# BMS_Enerdel_Adapter_Fuse_Holder_rev1.net
KiCad netlist of a schematic drawn in EAGLE
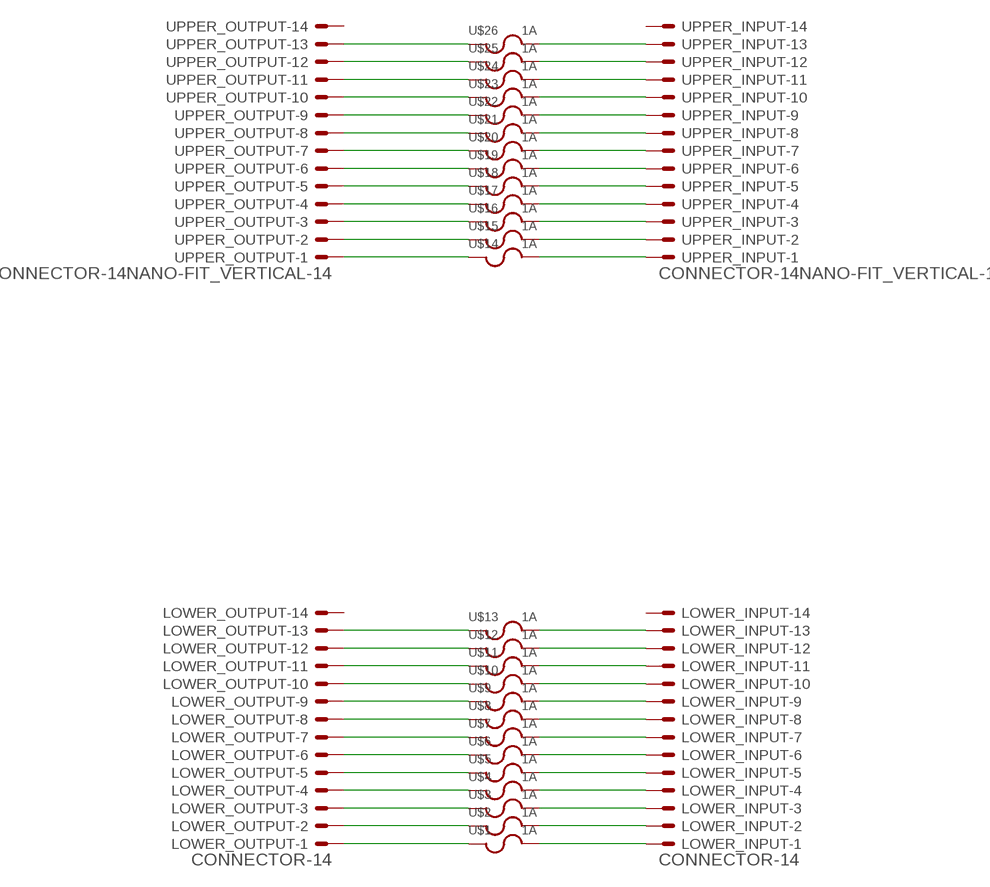
[diagram p0: schematic, sheet 1]

(export (version "E")
  (design (tool "Eeschema 10.0.6"))
  (components
    (comp (ref "LOWER_INPUT")
      (value "CONNECTOR-14")
      (footprint "eagle-import:MINIFIT_5566-14")
      (libsource (lib "eagle-import") (part "CONNECTOR-14"))
    )
    (comp (ref "LOWER_OUTPUT")
      (value "CONNECTOR-14")
      (footprint "eagle-import:MINIFIT_5566-14")
      (libsource (lib "eagle-import") (part "CONNECTOR-14"))
    )
    (comp (ref "U$1")
      (value "1A")
      (footprint "eagle-import:0751.0110")
      (libsource (lib "eagle-import") (part "FUSE_5X20MM"))
    )
    (comp (ref "U$2")
      (value "1A")
      (footprint "eagle-import:0751.0110")
      (libsource (lib "eagle-import") (part "FUSE_5X20MM"))
    )
    (comp (ref "U$3")
      (value "1A")
      (footprint "eagle-import:0751.0110")
      (libsource (lib "eagle-import") (part "FUSE_5X20MM"))
    )
    (comp (ref "U$4")
      (value "1A")
      (footprint "eagle-import:0751.0110")
      (libsource (lib "eagle-import") (part "FUSE_5X20MM"))
    )
    (comp (ref "U$5")
      (value "1A")
      (footprint "eagle-import:0751.0110")
      (libsource (lib "eagle-import") (part "FUSE_5X20MM"))
    )
    (comp (ref "U$6")
      (value "1A")
      (footprint "eagle-import:0751.0110")
      (libsource (lib "eagle-import") (part "FUSE_5X20MM"))
    )
    (comp (ref "U$7")
      (value "1A")
      (footprint "eagle-import:0751.0110")
      (libsource (lib "eagle-import") (part "FUSE_5X20MM"))
    )
    (comp (ref "U$8")
      (value "1A")
      (footprint "eagle-import:0751.0110")
      (libsource (lib "eagle-import") (part "FUSE_5X20MM"))
    )
    (comp (ref "U$9")
      (value "1A")
      (footprint "eagle-import:0751.0110")
      (libsource (lib "eagle-import") (part "FUSE_5X20MM"))
    )
    (comp (ref "U$10")
      (value "1A")
      (footprint "eagle-import:0751.0110")
      (libsource (lib "eagle-import") (part "FUSE_5X20MM"))
    )
    (comp (ref "U$11")
      (value "1A")
      (footprint "eagle-import:0751.0110")
      (libsource (lib "eagle-import") (part "FUSE_5X20MM"))
    )
    (comp (ref "U$12")
      (value "1A")
      (footprint "eagle-import:0751.0110")
      (libsource (lib "eagle-import") (part "FUSE_5X20MM"))
    )
    (comp (ref "U$13")
      (value "1A")
      (footprint "eagle-import:0751.0110")
      (libsource (lib "eagle-import") (part "FUSE_5X20MM"))
    )
    (comp (ref "U$14")
      (value "1A")
      (footprint "eagle-import:0751.0110")
      (libsource (lib "eagle-import") (part "FUSE_5X20MM"))
    )
    (comp (ref "U$15")
      (value "1A")
      (footprint "eagle-import:0751.0110")
      (libsource (lib "eagle-import") (part "FUSE_5X20MM"))
    )
    (comp (ref "U$16")
      (value "1A")
      (footprint "eagle-import:0751.0110")
      (libsource (lib "eagle-import") (part "FUSE_5X20MM"))
    )
    (comp (ref "U$17")
      (value "1A")
      (footprint "eagle-import:0751.0110")
      (libsource (lib "eagle-import") (part "FUSE_5X20MM"))
    )
    (comp (ref "U$18")
      (value "1A")
      (footprint "eagle-import:0751.0110")
      (libsource (lib "eagle-import") (part "FUSE_5X20MM"))
    )
    (comp (ref "U$19")
      (value "1A")
      (footprint "eagle-import:0751.0110")
      (libsource (lib "eagle-import") (part "FUSE_5X20MM"))
    )
    (comp (ref "U$20")
      (value "1A")
      (footprint "eagle-import:0751.0110")
      (libsource (lib "eagle-import") (part "FUSE_5X20MM"))
    )
    (comp (ref "U$21")
      (value "1A")
      (footprint "eagle-import:0751.0110")
      (libsource (lib "eagle-import") (part "FUSE_5X20MM"))
    )
    (comp (ref "U$22")
      (value "1A")
      (footprint "eagle-import:0751.0110")
      (libsource (lib "eagle-import") (part "FUSE_5X20MM"))
    )
    (comp (ref "U$23")
      (value "1A")
      (footprint "eagle-import:0751.0110")
      (libsource (lib "eagle-import") (part "FUSE_5X20MM"))
    )
    (comp (ref "U$24")
      (value "1A")
      (footprint "eagle-import:0751.0110")
      (libsource (lib "eagle-import") (part "FUSE_5X20MM"))
    )
    (comp (ref "U$25")
      (value "1A")
      (footprint "eagle-import:0751.0110")
      (libsource (lib "eagle-import") (part "FUSE_5X20MM"))
    )
    (comp (ref "U$26")
      (value "1A")
      (footprint "eagle-import:0751.0110")
      (libsource (lib "eagle-import") (part "FUSE_5X20MM"))
    )
    (comp (ref "UPPER_INPUT")
      (value "CONNECTOR-14NANO-FIT_VERTICAL-14")
      (footprint "eagle-import:NANO-FIT_VERTICAL-14")
      (libsource (lib "eagle-import") (part "CONNECTOR-14NANO-FIT_VERTICAL-14"))
    )
    (comp (ref "UPPER_OUTPUT")
      (value "CONNECTOR-14NANO-FIT_VERTICAL-14")
      (footprint "eagle-import:NANO-FIT_VERTICAL-14")
      (libsource (lib "eagle-import") (part "CONNECTOR-14NANO-FIT_VERTICAL-14"))
    )
  )
  (nets
    (net (code "1") (name "Net-(LOWER_INPUTA-S)") (class "Default")
      (node (ref "LOWER_INPUT") (pin "1") (pinfunction "S_1") (pintype "passive"))
      (node (ref "U$1") (pin "R1") (pinfunction "2_R1") (pintype "bidirectional"))
      (node (ref "U$1") (pin "R2") (pinfunction "2_R2") (pintype "bidirectional"))
    )
    (net (code "2") (name "Net-(LOWER_INPUTB-S)") (class "Default")
      (node (ref "LOWER_INPUT") (pin "10") (pinfunction "S_10") (pintype "passive"))
      (node (ref "U$10") (pin "R1") (pinfunction "2_R1") (pintype "bidirectional"))
      (node (ref "U$10") (pin "R2") (pinfunction "2_R2") (pintype "bidirectional"))
    )
    (net (code "3") (name "Net-(LOWER_INPUTC-S)") (class "Default")
      (node (ref "LOWER_INPUT") (pin "11") (pinfunction "S_11") (pintype "passive"))
      (node (ref "U$11") (pin "R1") (pinfunction "2_R1") (pintype "bidirectional"))
      (node (ref "U$11") (pin "R2") (pinfunction "2_R2") (pintype "bidirectional"))
    )
    (net (code "4") (name "Net-(LOWER_INPUTD-S)") (class "Default")
      (node (ref "LOWER_INPUT") (pin "12") (pinfunction "S_12") (pintype "passive"))
      (node (ref "U$12") (pin "R1") (pinfunction "2_R1") (pintype "bidirectional"))
      (node (ref "U$12") (pin "R2") (pinfunction "2_R2") (pintype "bidirectional"))
    )
    (net (code "5") (name "Net-(LOWER_INPUTE-S)") (class "Default")
      (node (ref "LOWER_INPUT") (pin "13") (pinfunction "S_13") (pintype "passive"))
      (node (ref "U$13") (pin "R1") (pinfunction "2_R1") (pintype "bidirectional"))
      (node (ref "U$13") (pin "R2") (pinfunction "2_R2") (pintype "bidirectional"))
    )
    (net (code "6") (name "Net-(LOWER_INPUTG-S)") (class "Default")
      (node (ref "LOWER_INPUT") (pin "2") (pinfunction "S_2") (pintype "passive"))
      (node (ref "U$2") (pin "R1") (pinfunction "2_R1") (pintype "bidirectional"))
      (node (ref "U$2") (pin "R2") (pinfunction "2_R2") (pintype "bidirectional"))
    )
    (net (code "7") (name "Net-(LOWER_INPUTH-S)") (class "Default")
      (node (ref "LOWER_INPUT") (pin "3") (pinfunction "S_3") (pintype "passive"))
      (node (ref "U$3") (pin "R1") (pinfunction "2_R1") (pintype "bidirectional"))
      (node (ref "U$3") (pin "R2") (pinfunction "2_R2") (pintype "bidirectional"))
    )
    (net (code "8") (name "Net-(LOWER_INPUTI-S)") (class "Default")
      (node (ref "LOWER_INPUT") (pin "4") (pinfunction "S_4") (pintype "passive"))
      (node (ref "U$4") (pin "R1") (pinfunction "2_R1") (pintype "bidirectional"))
      (node (ref "U$4") (pin "R2") (pinfunction "2_R2") (pintype "bidirectional"))
    )
    (net (code "9") (name "Net-(LOWER_INPUTJ-S)") (class "Default")
      (node (ref "LOWER_INPUT") (pin "5") (pinfunction "S_5") (pintype "passive"))
      (node (ref "U$5") (pin "R1") (pinfunction "2_R1") (pintype "bidirectional"))
      (node (ref "U$5") (pin "R2") (pinfunction "2_R2") (pintype "bidirectional"))
    )
    (net (code "10") (name "Net-(LOWER_INPUTK-S)") (class "Default")
      (node (ref "LOWER_INPUT") (pin "6") (pinfunction "S_6") (pintype "passive"))
      (node (ref "U$6") (pin "R1") (pinfunction "2_R1") (pintype "bidirectional"))
      (node (ref "U$6") (pin "R2") (pinfunction "2_R2") (pintype "bidirectional"))
    )
    (net (code "11") (name "Net-(LOWER_INPUTL-S)") (class "Default")
      (node (ref "LOWER_INPUT") (pin "7") (pinfunction "S_7") (pintype "passive"))
      (node (ref "U$7") (pin "R1") (pinfunction "2_R1") (pintype "bidirectional"))
      (node (ref "U$7") (pin "R2") (pinfunction "2_R2") (pintype "bidirectional"))
    )
    (net (code "12") (name "Net-(LOWER_INPUTM-S)") (class "Default")
      (node (ref "LOWER_INPUT") (pin "8") (pinfunction "S_8") (pintype "passive"))
      (node (ref "U$8") (pin "R1") (pinfunction "2_R1") (pintype "bidirectional"))
      (node (ref "U$8") (pin "R2") (pinfunction "2_R2") (pintype "bidirectional"))
    )
    (net (code "13") (name "Net-(LOWER_INPUTN-S)") (class "Default")
      (node (ref "LOWER_INPUT") (pin "9") (pinfunction "S_9") (pintype "passive"))
      (node (ref "U$9") (pin "R1") (pinfunction "2_R1") (pintype "bidirectional"))
      (node (ref "U$9") (pin "R2") (pinfunction "2_R2") (pintype "bidirectional"))
    )
    (net (code "14") (name "Net-(LOWER_OUTPUTA-S)") (class "Default")
      (node (ref "LOWER_OUTPUT") (pin "1") (pinfunction "S_1") (pintype "passive"))
      (node (ref "U$1") (pin "L1") (pinfunction "1_L1") (pintype "bidirectional"))
      (node (ref "U$1") (pin "L2") (pinfunction "1_L2") (pintype "bidirectional"))
    )
    (net (code "15") (name "Net-(LOWER_OUTPUTB-S)") (class "Default")
      (node (ref "LOWER_OUTPUT") (pin "10") (pinfunction "S_10") (pintype "passive"))
      (node (ref "U$10") (pin "L1") (pinfunction "1_L1") (pintype "bidirectional"))
      (node (ref "U$10") (pin "L2") (pinfunction "1_L2") (pintype "bidirectional"))
    )
    (net (code "16") (name "Net-(LOWER_OUTPUTC-S)") (class "Default")
      (node (ref "LOWER_OUTPUT") (pin "11") (pinfunction "S_11") (pintype "passive"))
      (node (ref "U$11") (pin "L1") (pinfunction "1_L1") (pintype "bidirectional"))
      (node (ref "U$11") (pin "L2") (pinfunction "1_L2") (pintype "bidirectional"))
    )
    (net (code "17") (name "Net-(LOWER_OUTPUTD-S)") (class "Default")
      (node (ref "LOWER_OUTPUT") (pin "12") (pinfunction "S_12") (pintype "passive"))
      (node (ref "U$12") (pin "L1") (pinfunction "1_L1") (pintype "bidirectional"))
      (node (ref "U$12") (pin "L2") (pinfunction "1_L2") (pintype "bidirectional"))
    )
    (net (code "18") (name "Net-(LOWER_OUTPUTE-S)") (class "Default")
      (node (ref "LOWER_OUTPUT") (pin "13") (pinfunction "S_13") (pintype "passive"))
      (node (ref "U$13") (pin "L1") (pinfunction "1_L1") (pintype "bidirectional"))
      (node (ref "U$13") (pin "L2") (pinfunction "1_L2") (pintype "bidirectional"))
    )
    (net (code "19") (name "Net-(LOWER_OUTPUTG-S)") (class "Default")
      (node (ref "LOWER_OUTPUT") (pin "2") (pinfunction "S_2") (pintype "passive"))
      (node (ref "U$2") (pin "L1") (pinfunction "1_L1") (pintype "bidirectional"))
      (node (ref "U$2") (pin "L2") (pinfunction "1_L2") (pintype "bidirectional"))
    )
    (net (code "20") (name "Net-(LOWER_OUTPUTH-S)") (class "Default")
      (node (ref "LOWER_OUTPUT") (pin "3") (pinfunction "S_3") (pintype "passive"))
      (node (ref "U$3") (pin "L1") (pinfunction "1_L1") (pintype "bidirectional"))
      (node (ref "U$3") (pin "L2") (pinfunction "1_L2") (pintype "bidirectional"))
    )
    (net (code "21") (name "Net-(LOWER_OUTPUTI-S)") (class "Default")
      (node (ref "LOWER_OUTPUT") (pin "4") (pinfunction "S_4") (pintype "passive"))
      (node (ref "U$4") (pin "L1") (pinfunction "1_L1") (pintype "bidirectional"))
      (node (ref "U$4") (pin "L2") (pinfunction "1_L2") (pintype "bidirectional"))
    )
    (net (code "22") (name "Net-(LOWER_OUTPUTJ-S)") (class "Default")
      (node (ref "LOWER_OUTPUT") (pin "5") (pinfunction "S_5") (pintype "passive"))
      (node (ref "U$5") (pin "L1") (pinfunction "1_L1") (pintype "bidirectional"))
      (node (ref "U$5") (pin "L2") (pinfunction "1_L2") (pintype "bidirectional"))
    )
    (net (code "23") (name "Net-(LOWER_OUTPUTK-S)") (class "Default")
      (node (ref "LOWER_OUTPUT") (pin "6") (pinfunction "S_6") (pintype "passive"))
      (node (ref "U$6") (pin "L1") (pinfunction "1_L1") (pintype "bidirectional"))
      (node (ref "U$6") (pin "L2") (pinfunction "1_L2") (pintype "bidirectional"))
    )
    (net (code "24") (name "Net-(LOWER_OUTPUTL-S)") (class "Default")
      (node (ref "LOWER_OUTPUT") (pin "7") (pinfunction "S_7") (pintype "passive"))
      (node (ref "U$7") (pin "L1") (pinfunction "1_L1") (pintype "bidirectional"))
      (node (ref "U$7") (pin "L2") (pinfunction "1_L2") (pintype "bidirectional"))
    )
    (net (code "25") (name "Net-(LOWER_OUTPUTM-S)") (class "Default")
      (node (ref "LOWER_OUTPUT") (pin "8") (pinfunction "S_8") (pintype "passive"))
      (node (ref "U$8") (pin "L1") (pinfunction "1_L1") (pintype "bidirectional"))
      (node (ref "U$8") (pin "L2") (pinfunction "1_L2") (pintype "bidirectional"))
    )
    (net (code "26") (name "Net-(LOWER_OUTPUTN-S)") (class "Default")
      (node (ref "LOWER_OUTPUT") (pin "9") (pinfunction "S_9") (pintype "passive"))
      (node (ref "U$9") (pin "L1") (pinfunction "1_L1") (pintype "bidirectional"))
      (node (ref "U$9") (pin "L2") (pinfunction "1_L2") (pintype "bidirectional"))
    )
    (net (code "27") (name "Net-(UPPER_INPUTA-S)") (class "Default")
      (node (ref "U$14") (pin "R1") (pinfunction "2_R1") (pintype "bidirectional"))
      (node (ref "U$14") (pin "R2") (pinfunction "2_R2") (pintype "bidirectional"))
      (node (ref "UPPER_INPUT") (pin "P$1") (pinfunction "S_P$1") (pintype "passive"))
    )
    (net (code "28") (name "Net-(UPPER_INPUTB-S)") (class "Default")
      (node (ref "U$23") (pin "R1") (pinfunction "2_R1") (pintype "bidirectional"))
      (node (ref "U$23") (pin "R2") (pinfunction "2_R2") (pintype "bidirectional"))
      (node (ref "UPPER_INPUT") (pin "P$10") (pinfunction "S_P$10") (pintype "passive"))
    )
    (net (code "29") (name "Net-(UPPER_INPUTC-S)") (class "Default")
      (node (ref "U$24") (pin "R1") (pinfunction "2_R1") (pintype "bidirectional"))
      (node (ref "U$24") (pin "R2") (pinfunction "2_R2") (pintype "bidirectional"))
      (node (ref "UPPER_INPUT") (pin "P$11") (pinfunction "S_P$11") (pintype "passive"))
    )
    (net (code "30") (name "Net-(UPPER_INPUTD-S)") (class "Default")
      (node (ref "U$25") (pin "R1") (pinfunction "2_R1") (pintype "bidirectional"))
      (node (ref "U$25") (pin "R2") (pinfunction "2_R2") (pintype "bidirectional"))
      (node (ref "UPPER_INPUT") (pin "P$12") (pinfunction "S_P$12") (pintype "passive"))
    )
    (net (code "31") (name "Net-(UPPER_INPUTE-S)") (class "Default")
      (node (ref "U$26") (pin "R1") (pinfunction "2_R1") (pintype "bidirectional"))
      (node (ref "U$26") (pin "R2") (pinfunction "2_R2") (pintype "bidirectional"))
      (node (ref "UPPER_INPUT") (pin "P$13") (pinfunction "S_P$13") (pintype "passive"))
    )
    (net (code "32") (name "Net-(UPPER_INPUTG-S)") (class "Default")
      (node (ref "U$15") (pin "R1") (pinfunction "2_R1") (pintype "bidirectional"))
      (node (ref "U$15") (pin "R2") (pinfunction "2_R2") (pintype "bidirectional"))
      (node (ref "UPPER_INPUT") (pin "P$2") (pinfunction "S_P$2") (pintype "passive"))
    )
    (net (code "33") (name "Net-(UPPER_INPUTH-S)") (class "Default")
      (node (ref "U$16") (pin "R1") (pinfunction "2_R1") (pintype "bidirectional"))
      (node (ref "U$16") (pin "R2") (pinfunction "2_R2") (pintype "bidirectional"))
      (node (ref "UPPER_INPUT") (pin "P$3") (pinfunction "S_P$3") (pintype "passive"))
    )
    (net (code "34") (name "Net-(UPPER_INPUTI-S)") (class "Default")
      (node (ref "U$17") (pin "R1") (pinfunction "2_R1") (pintype "bidirectional"))
      (node (ref "U$17") (pin "R2") (pinfunction "2_R2") (pintype "bidirectional"))
      (node (ref "UPPER_INPUT") (pin "P$4") (pinfunction "S_P$4") (pintype "passive"))
    )
    (net (code "35") (name "Net-(UPPER_INPUTJ-S)") (class "Default")
      (node (ref "U$18") (pin "R1") (pinfunction "2_R1") (pintype "bidirectional"))
      (node (ref "U$18") (pin "R2") (pinfunction "2_R2") (pintype "bidirectional"))
      (node (ref "UPPER_INPUT") (pin "P$5") (pinfunction "S_P$5") (pintype "passive"))
    )
    (net (code "36") (name "Net-(UPPER_INPUTK-S)") (class "Default")
      (node (ref "U$19") (pin "R1") (pinfunction "2_R1") (pintype "bidirectional"))
      (node (ref "U$19") (pin "R2") (pinfunction "2_R2") (pintype "bidirectional"))
      (node (ref "UPPER_INPUT") (pin "P$6") (pinfunction "S_P$6") (pintype "passive"))
    )
    (net (code "37") (name "Net-(UPPER_INPUTL-S)") (class "Default")
      (node (ref "U$20") (pin "R1") (pinfunction "2_R1") (pintype "bidirectional"))
      (node (ref "U$20") (pin "R2") (pinfunction "2_R2") (pintype "bidirectional"))
      (node (ref "UPPER_INPUT") (pin "P$7") (pinfunction "S_P$7") (pintype "passive"))
    )
    (net (code "38") (name "Net-(UPPER_INPUTM-S)") (class "Default")
      (node (ref "U$21") (pin "R1") (pinfunction "2_R1") (pintype "bidirectional"))
      (node (ref "U$21") (pin "R2") (pinfunction "2_R2") (pintype "bidirectional"))
      (node (ref "UPPER_INPUT") (pin "P$8") (pinfunction "S_P$8") (pintype "passive"))
    )
    (net (code "39") (name "Net-(UPPER_INPUTN-S)") (class "Default")
      (node (ref "U$22") (pin "R1") (pinfunction "2_R1") (pintype "bidirectional"))
      (node (ref "U$22") (pin "R2") (pinfunction "2_R2") (pintype "bidirectional"))
      (node (ref "UPPER_INPUT") (pin "P$9") (pinfunction "S_P$9") (pintype "passive"))
    )
    (net (code "40") (name "Net-(UPPER_OUTPUTA-S)") (class "Default")
      (node (ref "U$14") (pin "L1") (pinfunction "1_L1") (pintype "bidirectional"))
      (node (ref "U$14") (pin "L2") (pinfunction "1_L2") (pintype "bidirectional"))
      (node (ref "UPPER_OUTPUT") (pin "P$1") (pinfunction "S_P$1") (pintype "passive"))
    )
    (net (code "41") (name "Net-(UPPER_OUTPUTB-S)") (class "Default")
      (node (ref "U$23") (pin "L1") (pinfunction "1_L1") (pintype "bidirectional"))
      (node (ref "U$23") (pin "L2") (pinfunction "1_L2") (pintype "bidirectional"))
      (node (ref "UPPER_OUTPUT") (pin "P$10") (pinfunction "S_P$10") (pintype "passive"))
    )
    (net (code "42") (name "Net-(UPPER_OUTPUTC-S)") (class "Default")
      (node (ref "U$24") (pin "L1") (pinfunction "1_L1") (pintype "bidirectional"))
      (node (ref "U$24") (pin "L2") (pinfunction "1_L2") (pintype "bidirectional"))
      (node (ref "UPPER_OUTPUT") (pin "P$11") (pinfunction "S_P$11") (pintype "passive"))
    )
    (net (code "43") (name "Net-(UPPER_OUTPUTD-S)") (class "Default")
      (node (ref "U$25") (pin "L1") (pinfunction "1_L1") (pintype "bidirectional"))
      (node (ref "U$25") (pin "L2") (pinfunction "1_L2") (pintype "bidirectional"))
      (node (ref "UPPER_OUTPUT") (pin "P$12") (pinfunction "S_P$12") (pintype "passive"))
    )
    (net (code "44") (name "Net-(UPPER_OUTPUTE-S)") (class "Default")
      (node (ref "U$26") (pin "L1") (pinfunction "1_L1") (pintype "bidirectional"))
      (node (ref "U$26") (pin "L2") (pinfunction "1_L2") (pintype "bidirectional"))
      (node (ref "UPPER_OUTPUT") (pin "P$13") (pinfunction "S_P$13") (pintype "passive"))
    )
    (net (code "45") (name "Net-(UPPER_OUTPUTG-S)") (class "Default")
      (node (ref "U$15") (pin "L1") (pinfunction "1_L1") (pintype "bidirectional"))
      (node (ref "U$15") (pin "L2") (pinfunction "1_L2") (pintype "bidirectional"))
      (node (ref "UPPER_OUTPUT") (pin "P$2") (pinfunction "S_P$2") (pintype "passive"))
    )
    (net (code "46") (name "Net-(UPPER_OUTPUTH-S)") (class "Default")
      (node (ref "U$16") (pin "L1") (pinfunction "1_L1") (pintype "bidirectional"))
      (node (ref "U$16") (pin "L2") (pinfunction "1_L2") (pintype "bidirectional"))
      (node (ref "UPPER_OUTPUT") (pin "P$3") (pinfunction "S_P$3") (pintype "passive"))
    )
    (net (code "47") (name "Net-(UPPER_OUTPUTI-S)") (class "Default")
      (node (ref "U$17") (pin "L1") (pinfunction "1_L1") (pintype "bidirectional"))
      (node (ref "U$17") (pin "L2") (pinfunction "1_L2") (pintype "bidirectional"))
      (node (ref "UPPER_OUTPUT") (pin "P$4") (pinfunction "S_P$4") (pintype "passive"))
    )
    (net (code "48") (name "Net-(UPPER_OUTPUTJ-S)") (class "Default")
      (node (ref "U$18") (pin "L1") (pinfunction "1_L1") (pintype "bidirectional"))
      (node (ref "U$18") (pin "L2") (pinfunction "1_L2") (pintype "bidirectional"))
      (node (ref "UPPER_OUTPUT") (pin "P$5") (pinfunction "S_P$5") (pintype "passive"))
    )
    (net (code "49") (name "Net-(UPPER_OUTPUTK-S)") (class "Default")
      (node (ref "U$19") (pin "L1") (pinfunction "1_L1") (pintype "bidirectional"))
      (node (ref "U$19") (pin "L2") (pinfunction "1_L2") (pintype "bidirectional"))
      (node (ref "UPPER_OUTPUT") (pin "P$6") (pinfunction "S_P$6") (pintype "passive"))
    )
    (net (code "50") (name "Net-(UPPER_OUTPUTL-S)") (class "Default")
      (node (ref "U$20") (pin "L1") (pinfunction "1_L1") (pintype "bidirectional"))
      (node (ref "U$20") (pin "L2") (pinfunction "1_L2") (pintype "bidirectional"))
      (node (ref "UPPER_OUTPUT") (pin "P$7") (pinfunction "S_P$7") (pintype "passive"))
    )
    (net (code "51") (name "Net-(UPPER_OUTPUTM-S)") (class "Default")
      (node (ref "U$21") (pin "L1") (pinfunction "1_L1") (pintype "bidirectional"))
      (node (ref "U$21") (pin "L2") (pinfunction "1_L2") (pintype "bidirectional"))
      (node (ref "UPPER_OUTPUT") (pin "P$8") (pinfunction "S_P$8") (pintype "passive"))
    )
    (net (code "52") (name "Net-(UPPER_OUTPUTN-S)") (class "Default")
      (node (ref "U$22") (pin "L1") (pinfunction "1_L1") (pintype "bidirectional"))
      (node (ref "U$22") (pin "L2") (pinfunction "1_L2") (pintype "bidirectional"))
      (node (ref "UPPER_OUTPUT") (pin "P$9") (pinfunction "S_P$9") (pintype "passive"))
    )
    (net (code "53") (name "unconnected-(LOWER_INPUTF-S-Pad14)") (class "Default")
      (node (ref "LOWER_INPUT") (pin "14") (pinfunction "S_14") (pintype "passive"))
    )
    (net (code "54") (name "unconnected-(LOWER_OUTPUTF-S-Pad14)") (class "Default")
      (node (ref "LOWER_OUTPUT") (pin "14") (pinfunction "S_14") (pintype "passive"))
    )
    (net (code "55") (name "unconnected-(UPPER_INPUTF-S-PadP$14)") (class "Default")
      (node (ref "UPPER_INPUT") (pin "P$14") (pinfunction "S_P$14") (pintype "passive"))
    )
    (net (code "56") (name "unconnected-(UPPER_OUTPUTF-S-PadP$14)") (class "Default")
      (node (ref "UPPER_OUTPUT") (pin "P$14") (pinfunction "S_P$14") (pintype "passive"))
    )
  )
)
